# Mosaic-G5.net
KiCad netlist of a schematic drawn in Altium Designer
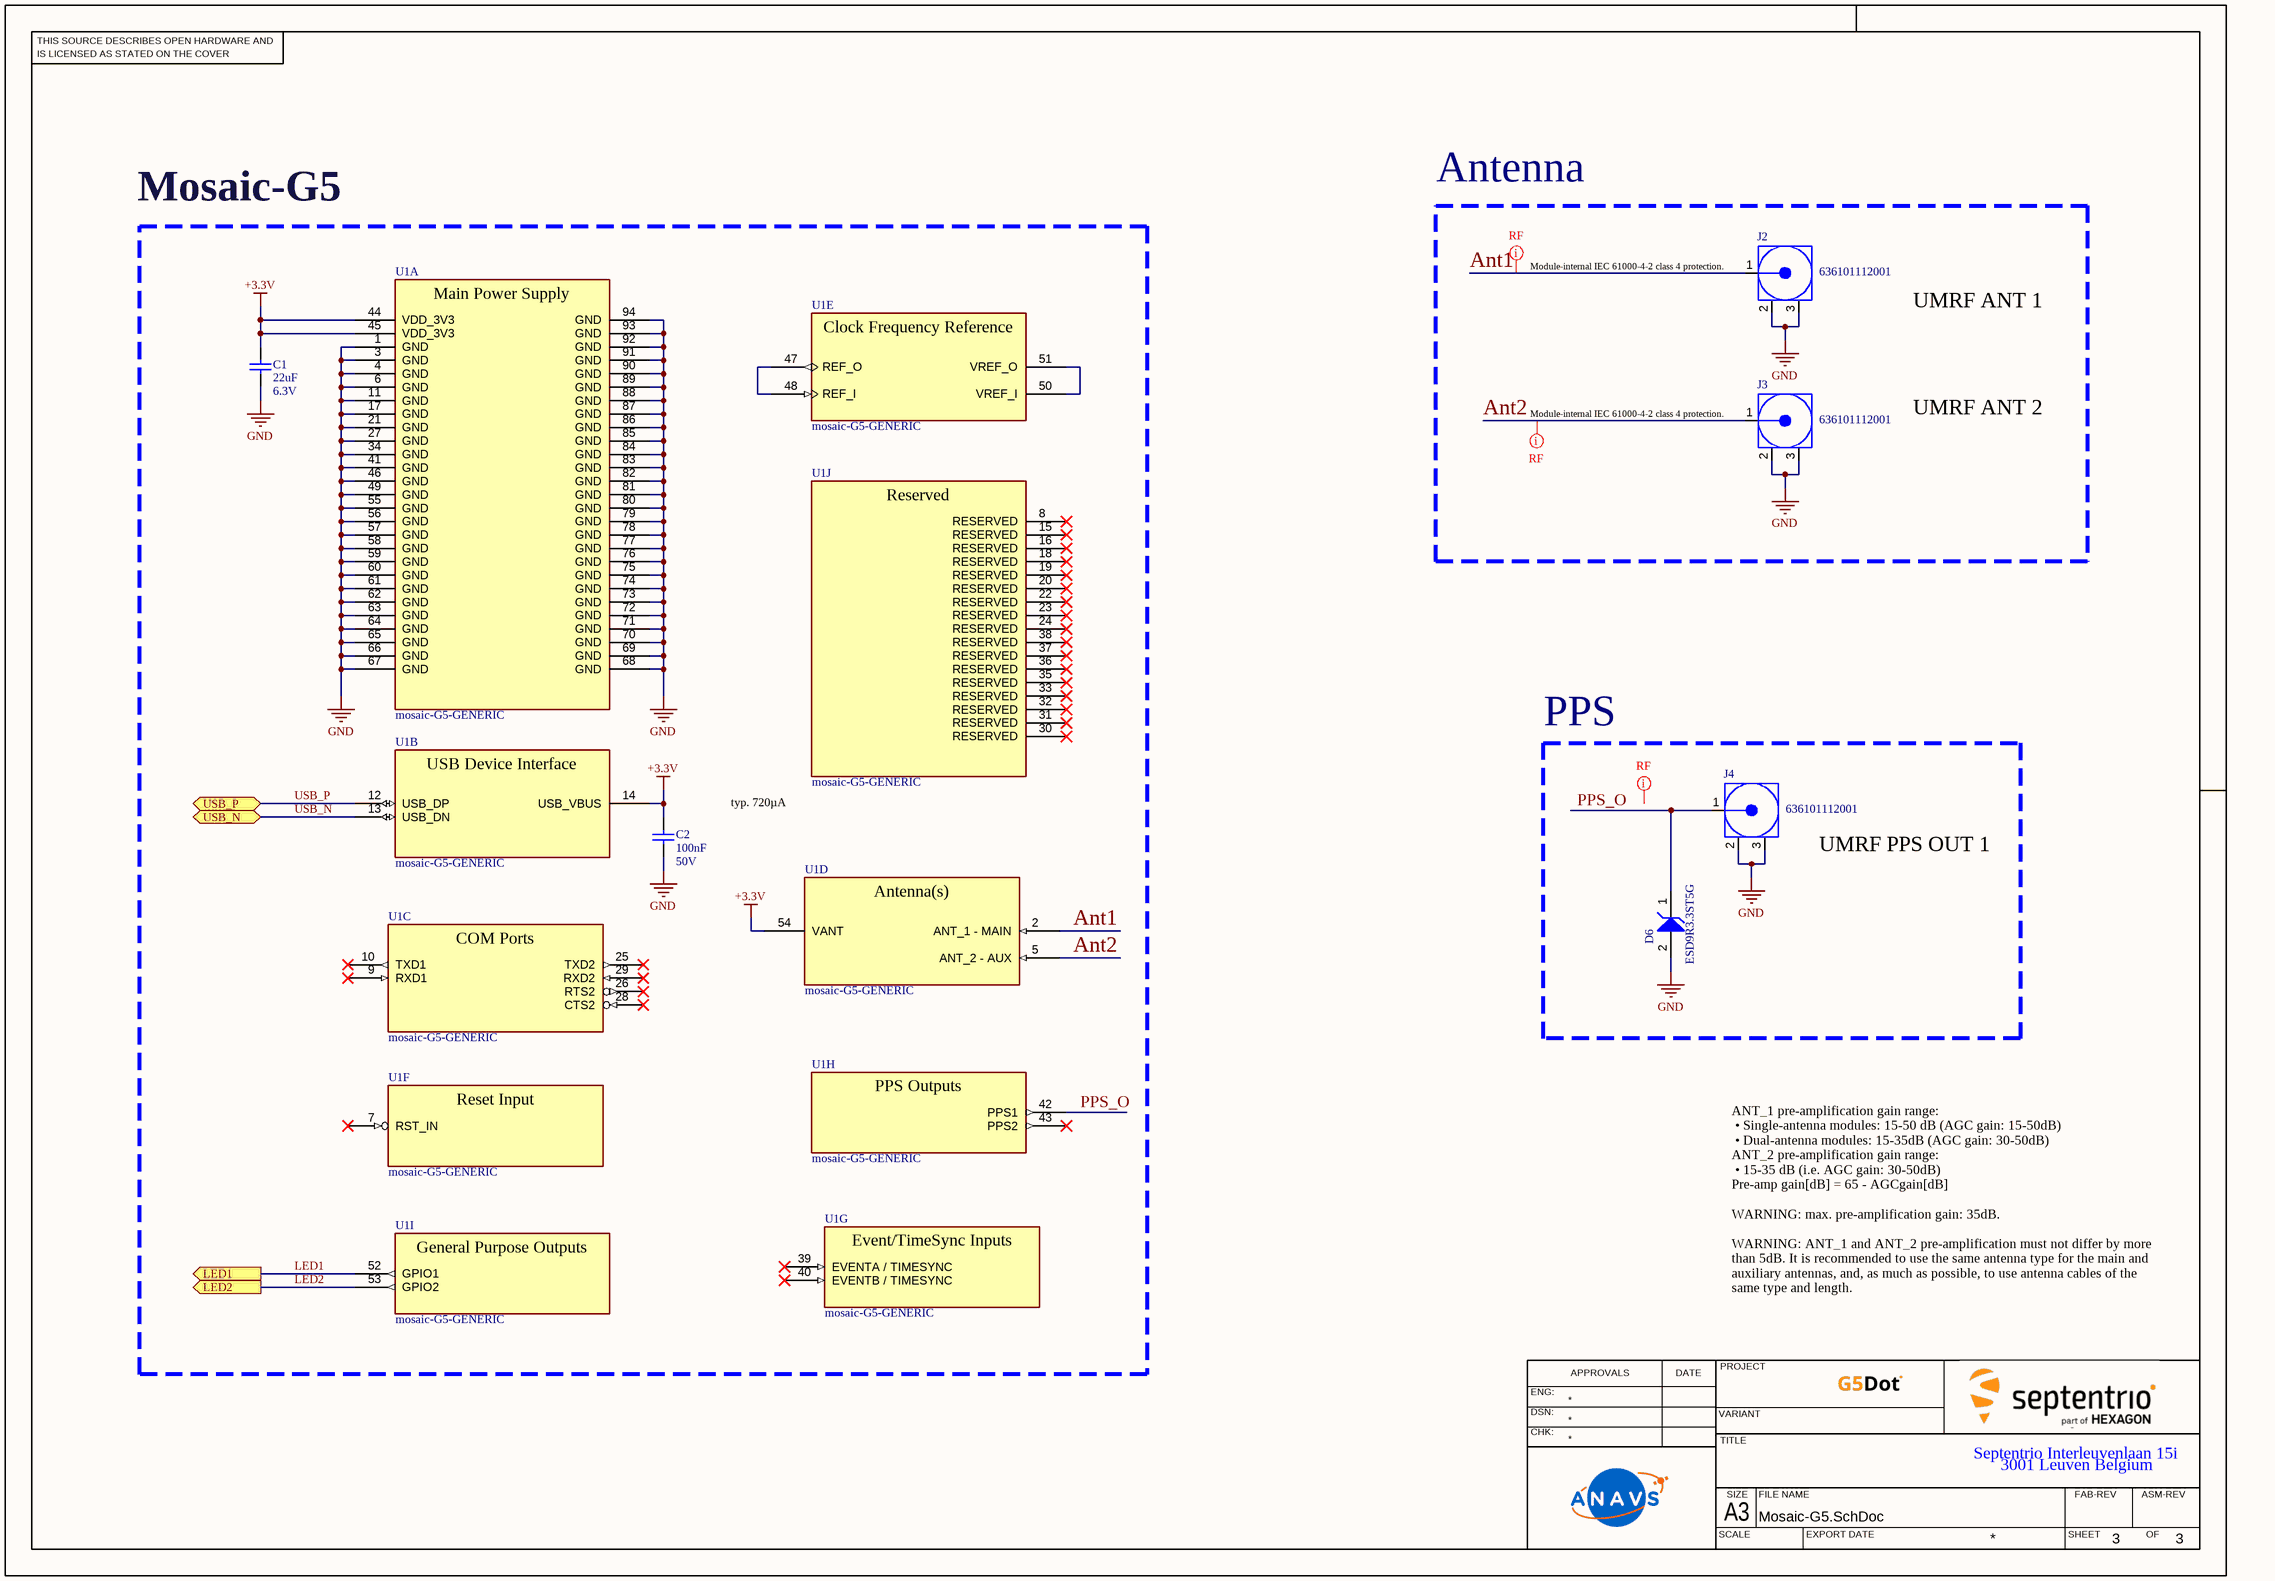
[diagram p0: Mosaic-G5.SchDoc]

(export (version "E")
  (design (tool "Eeschema 10.0.6"))
  (components
    (comp (ref "C1")
      (value "22uF")
      (footprint "CAPC1608X100X20ML10")
      (description "MLCC, 22 uF, 0603, 6.3 V, 20%, X5R")
      (fields
        (field (name "VOLTAGE") "6.3V")
        (field (name "TOLERANCE") "20%")
        (field (name "Comment") "C1608X5R0J226M080AC")
      )
      (libsource (lib "ANavS GmbH") (part "CAP"))
    )
    (comp (ref "C2")
      (value "GCM155R71H104KE02D")
      (footprint "CAP0402C")
      (description "MLCC, 100 nF, 0402, 50 V, 10%, X7R")
      (fields
        (field (name "CAPACITANCE") "100nF")
        (field (name "TOLERANCE") "10%")
        (field (name "VOLTAGE") "50V")
      )
      (libsource (lib "ANavS GmbH") (part "CAP"))
    )
    (comp (ref "D6")
      (value "ESD9R3.3ST5G")
      (footprint "ONSC-SOD-923-2-514AB-01_V")
      (description "ESD9R3.3S Series 4.8 V 0.5 pF Uni-Directional ESD Protection Diode - SOD-923")
      (libsource (lib "ANavS GmbH") (part "ONSC-K1A2-2_A"))
    )
    (comp (ref "J2")
      (value "636101112001")
      (footprint "63610111x001")
      (description "Rf Conn, Umrf, Jack, 50 Ohm, Pcb Rohs Compliant: Yes")
      (libsource (lib "ANavS GmbH") (part "Plug_2GND"))
    )
    (comp (ref "J3")
      (value "636101112001")
      (footprint "63610111x001")
      (description "Rf Conn, Umrf, Jack, 50 Ohm, Pcb Rohs Compliant: Yes")
      (libsource (lib "ANavS GmbH") (part "Plug_2GND"))
    )
    (comp (ref "J4")
      (value "636101112001")
      (footprint "63610111x001")
      (description "Rf Conn, Umrf, Jack, 50 Ohm, Pcb Rohs Compliant: Yes")
      (libsource (lib "ANavS GmbH") (part "Plug_2GND"))
    )
    (comp (ref "U1")
      (value "mosaic-G5-GENERIC")
      (footprint "mosaic-G5-GENERIC-Footprint")
      (description "mosaic-G5 GNSS Module - Low-power multi-band multi-constellation GNSS receiver.")
      (fields (field (name "MANUFACTURER") "septentrio"))
      (libsource (lib "") (part "mosaic-G5-Symbol_1"))
    )
  )
  (nets
    (net (code "1") (name "+3.3V") (class "Default")
      (node (ref "C1") (pin "2") (pinfunction "2_2") (pintype "passive"))
      (node (ref "C2") (pin "2") (pinfunction "2_2") (pintype "passive"))
      (node (ref "U1") (pin "14") (pinfunction "USB_VBUS_14") (pintype "power_in"))
      (node (ref "U1") (pin "44") (pinfunction "VDD_3V3_44") (pintype "power_in"))
      (node (ref "U1") (pin "45") (pinfunction "VDD_3V3_45") (pintype "power_in"))
      (node (ref "U1") (pin "54") (pinfunction "VANT_54") (pintype "power_in"))
    )
    (net (code "2") (name "/Ant1") (class "Default")
      (node (ref "J2") (pin "1") (pinfunction "Signal_1") (pintype "passive"))
      (node (ref "U1") (pin "2") (pinfunction "ANT_1_-_MAIN_2") (pintype "input"))
    )
    (net (code "3") (name "/Ant2") (class "Default")
      (node (ref "J3") (pin "1") (pinfunction "Signal_1") (pintype "passive"))
      (node (ref "U1") (pin "5") (pinfunction "ANT_2_-_AUX_5") (pintype "input"))
    )
    (net (code "4") (name "/LED1") (class "Default")
      (node (ref "U1") (pin "52") (pinfunction "GPIO1_52") (pintype "output"))
    )
    (net (code "5") (name "/LED2") (class "Default")
      (node (ref "U1") (pin "53") (pinfunction "GPIO2_53") (pintype "output"))
    )
    (net (code "6") (name "/PPS_O") (class "Default")
      (node (ref "D6") (pin "1") (pinfunction "K_1") (pintype "passive"))
      (node (ref "J4") (pin "1") (pinfunction "Signal_1") (pintype "passive"))
      (node (ref "U1") (pin "42") (pinfunction "PPS1_42") (pintype "output"))
    )
    (net (code "7") (name "/USB_N") (class "Default")
      (node (ref "U1") (pin "13") (pinfunction "USB_DN_13") (pintype "bidirectional"))
    )
    (net (code "8") (name "/USB_P") (class "Default")
      (node (ref "U1") (pin "12") (pinfunction "USB_DP_12") (pintype "bidirectional"))
    )
    (net (code "9") (name "GND") (class "Default")
      (node (ref "C1") (pin "1") (pinfunction "1_1") (pintype "passive"))
      (node (ref "C2") (pin "1") (pinfunction "1_1") (pintype "passive"))
      (node (ref "D6") (pin "2") (pinfunction "A_2") (pintype "passive"))
      (node (ref "J2") (pin "2") (pinfunction "GND_2") (pintype "passive"))
      (node (ref "J2") (pin "3") (pinfunction "GND_3") (pintype "passive"))
      (node (ref "J3") (pin "2") (pinfunction "GND_2") (pintype "passive"))
      (node (ref "J3") (pin "3") (pinfunction "GND_3") (pintype "passive"))
      (node (ref "J4") (pin "2") (pinfunction "GND_2") (pintype "passive"))
      (node (ref "J4") (pin "3") (pinfunction "GND_3") (pintype "passive"))
      (node (ref "U1") (pin "1") (pinfunction "GND_1") (pintype "power_in"))
      (node (ref "U1") (pin "11") (pinfunction "GND_11") (pintype "power_in"))
      (node (ref "U1") (pin "17") (pinfunction "GND_17") (pintype "power_in"))
      (node (ref "U1") (pin "21") (pinfunction "GND_21") (pintype "power_in"))
      (node (ref "U1") (pin "27") (pinfunction "GND_27") (pintype "power_in"))
      (node (ref "U1") (pin "3") (pinfunction "GND_3") (pintype "power_in"))
      (node (ref "U1") (pin "34") (pinfunction "GND_34") (pintype "power_in"))
      (node (ref "U1") (pin "4") (pinfunction "GND_4") (pintype "power_in"))
      (node (ref "U1") (pin "41") (pinfunction "GND_41") (pintype "power_in"))
      (node (ref "U1") (pin "46") (pinfunction "GND_46") (pintype "power_in"))
      (node (ref "U1") (pin "49") (pinfunction "GND_49") (pintype "power_in"))
      (node (ref "U1") (pin "55") (pinfunction "GND_55") (pintype "power_in"))
      (node (ref "U1") (pin "56") (pinfunction "GND_56") (pintype "power_in"))
      (node (ref "U1") (pin "57") (pinfunction "GND_57") (pintype "power_in"))
      (node (ref "U1") (pin "58") (pinfunction "GND_58") (pintype "power_in"))
      (node (ref "U1") (pin "59") (pinfunction "GND_59") (pintype "power_in"))
      (node (ref "U1") (pin "6") (pinfunction "GND_6") (pintype "power_in"))
      (node (ref "U1") (pin "60") (pinfunction "GND_60") (pintype "power_in"))
      (node (ref "U1") (pin "61") (pinfunction "GND_61") (pintype "power_in"))
      (node (ref "U1") (pin "62") (pinfunction "GND_62") (pintype "power_in"))
      (node (ref "U1") (pin "63") (pinfunction "GND_63") (pintype "power_in"))
      (node (ref "U1") (pin "64") (pinfunction "GND_64") (pintype "power_in"))
      (node (ref "U1") (pin "65") (pinfunction "GND_65") (pintype "power_in"))
      (node (ref "U1") (pin "66") (pinfunction "GND_66") (pintype "power_in"))
      (node (ref "U1") (pin "67") (pinfunction "GND_67") (pintype "power_in"))
      (node (ref "U1") (pin "68") (pinfunction "GND_68") (pintype "power_in"))
      (node (ref "U1") (pin "69") (pinfunction "GND_69") (pintype "power_in"))
      (node (ref "U1") (pin "70") (pinfunction "GND_70") (pintype "power_in"))
      (node (ref "U1") (pin "71") (pinfunction "GND_71") (pintype "power_in"))
      (node (ref "U1") (pin "72") (pinfunction "GND_72") (pintype "power_in"))
      (node (ref "U1") (pin "73") (pinfunction "GND_73") (pintype "power_in"))
      (node (ref "U1") (pin "74") (pinfunction "GND_74") (pintype "power_in"))
      (node (ref "U1") (pin "75") (pinfunction "GND_75") (pintype "power_in"))
      (node (ref "U1") (pin "76") (pinfunction "GND_76") (pintype "power_in"))
      (node (ref "U1") (pin "77") (pinfunction "GND_77") (pintype "power_in"))
      (node (ref "U1") (pin "78") (pinfunction "GND_78") (pintype "power_in"))
      (node (ref "U1") (pin "79") (pinfunction "GND_79") (pintype "power_in"))
      (node (ref "U1") (pin "80") (pinfunction "GND_80") (pintype "power_in"))
      (node (ref "U1") (pin "81") (pinfunction "GND_81") (pintype "power_in"))
      (node (ref "U1") (pin "82") (pinfunction "GND_82") (pintype "power_in"))
      (node (ref "U1") (pin "83") (pinfunction "GND_83") (pintype "power_in"))
      (node (ref "U1") (pin "84") (pinfunction "GND_84") (pintype "power_in"))
      (node (ref "U1") (pin "85") (pinfunction "GND_85") (pintype "power_in"))
      (node (ref "U1") (pin "86") (pinfunction "GND_86") (pintype "power_in"))
      (node (ref "U1") (pin "87") (pinfunction "GND_87") (pintype "power_in"))
      (node (ref "U1") (pin "88") (pinfunction "GND_88") (pintype "power_in"))
      (node (ref "U1") (pin "89") (pinfunction "GND_89") (pintype "power_in"))
      (node (ref "U1") (pin "90") (pinfunction "GND_90") (pintype "power_in"))
      (node (ref "U1") (pin "91") (pinfunction "GND_91") (pintype "power_in"))
      (node (ref "U1") (pin "92") (pinfunction "GND_92") (pintype "power_in"))
      (node (ref "U1") (pin "93") (pinfunction "GND_93") (pintype "power_in"))
      (node (ref "U1") (pin "94") (pinfunction "GND_94") (pintype "power_in"))
    )
    (net (code "10") (name "Net-(U1E-REF_I)") (class "Default")
      (node (ref "U1") (pin "47") (pinfunction "REF_O_47") (pintype "output"))
      (node (ref "U1") (pin "48") (pinfunction "REF_I_48") (pintype "input"))
    )
    (net (code "11") (name "Net-(U1E-VREF_I)") (class "Default")
      (node (ref "U1") (pin "50") (pinfunction "VREF_I_50") (pintype "power_in"))
      (node (ref "U1") (pin "51") (pinfunction "VREF_O_51") (pintype "power_in"))
    )
    (net (code "12") (name "unconnected-(U1C-CTS2-Pad28)") (class "Default")
      (node (ref "U1") (pin "28") (pinfunction "CTS2_28") (pintype "input+no_connect"))
    )
    (net (code "13") (name "unconnected-(U1C-RTS2-Pad26)") (class "Default")
      (node (ref "U1") (pin "26") (pinfunction "RTS2_26") (pintype "output+no_connect"))
    )
    (net (code "14") (name "unconnected-(U1C-RXD1-Pad9)") (class "Default")
      (node (ref "U1") (pin "9") (pinfunction "RXD1_9") (pintype "input+no_connect"))
    )
    (net (code "15") (name "unconnected-(U1C-RXD2-Pad29)") (class "Default")
      (node (ref "U1") (pin "29") (pinfunction "RXD2_29") (pintype "input+no_connect"))
    )
    (net (code "16") (name "unconnected-(U1C-TXD1-Pad10)") (class "Default")
      (node (ref "U1") (pin "10") (pinfunction "TXD1_10") (pintype "output+no_connect"))
    )
    (net (code "17") (name "unconnected-(U1C-TXD2-Pad25)") (class "Default")
      (node (ref "U1") (pin "25") (pinfunction "TXD2_25") (pintype "output+no_connect"))
    )
    (net (code "18") (name "unconnected-(U1F-RST_IN-Pad7)") (class "Default")
      (node (ref "U1") (pin "7") (pinfunction "RST_IN_7") (pintype "input+no_connect"))
    )
    (net (code "19") (name "unconnected-(U1G-EVENTA_{slash}_TIMESYNC-Pad39)") (class "Default")
      (node (ref "U1") (pin "39") (pinfunction "EVENTA_/_TIMESYNC_39") (pintype "input+no_connect"))
    )
    (net (code "20") (name "unconnected-(U1G-EVENTB_{slash}_TIMESYNC-Pad40)") (class "Default")
      (node (ref "U1") (pin "40") (pinfunction "EVENTB_/_TIMESYNC_40") (pintype "input+no_connect"))
    )
    (net (code "21") (name "unconnected-(U1H-PPS2-Pad43)") (class "Default")
      (node (ref "U1") (pin "43") (pinfunction "PPS2_43") (pintype "output+no_connect"))
    )
    (net (code "22") (name "unconnected-(U1J-RESERVED-Pad8)") (class "Default")
      (node (ref "U1") (pin "8") (pinfunction "RESERVED_8") (pintype "passive+no_connect"))
    )
    (net (code "23") (name "unconnected-(U1J-RESERVED-Pad15)") (class "Default")
      (node (ref "U1") (pin "15") (pinfunction "RESERVED_15") (pintype "passive+no_connect"))
    )
    (net (code "24") (name "unconnected-(U1J-RESERVED-Pad16)") (class "Default")
      (node (ref "U1") (pin "16") (pinfunction "RESERVED_16") (pintype "passive+no_connect"))
    )
    (net (code "25") (name "unconnected-(U1J-RESERVED-Pad18)") (class "Default")
      (node (ref "U1") (pin "18") (pinfunction "RESERVED_18") (pintype "passive+no_connect"))
    )
    (net (code "26") (name "unconnected-(U1J-RESERVED-Pad19)") (class "Default")
      (node (ref "U1") (pin "19") (pinfunction "RESERVED_19") (pintype "passive+no_connect"))
    )
    (net (code "27") (name "unconnected-(U1J-RESERVED-Pad20)") (class "Default")
      (node (ref "U1") (pin "20") (pinfunction "RESERVED_20") (pintype "passive+no_connect"))
    )
    (net (code "28") (name "unconnected-(U1J-RESERVED-Pad22)") (class "Default")
      (node (ref "U1") (pin "22") (pinfunction "RESERVED_22") (pintype "passive+no_connect"))
    )
    (net (code "29") (name "unconnected-(U1J-RESERVED-Pad23)") (class "Default")
      (node (ref "U1") (pin "23") (pinfunction "RESERVED_23") (pintype "passive+no_connect"))
    )
    (net (code "30") (name "unconnected-(U1J-RESERVED-Pad24)") (class "Default")
      (node (ref "U1") (pin "24") (pinfunction "RESERVED_24") (pintype "passive+no_connect"))
    )
    (net (code "31") (name "unconnected-(U1J-RESERVED-Pad30)") (class "Default")
      (node (ref "U1") (pin "30") (pinfunction "RESERVED_30") (pintype "passive+no_connect"))
    )
    (net (code "32") (name "unconnected-(U1J-RESERVED-Pad31)") (class "Default")
      (node (ref "U1") (pin "31") (pinfunction "RESERVED_31") (pintype "passive+no_connect"))
    )
    (net (code "33") (name "unconnected-(U1J-RESERVED-Pad32)") (class "Default")
      (node (ref "U1") (pin "32") (pinfunction "RESERVED_32") (pintype "passive+no_connect"))
    )
    (net (code "34") (name "unconnected-(U1J-RESERVED-Pad33)") (class "Default")
      (node (ref "U1") (pin "33") (pinfunction "RESERVED_33") (pintype "passive+no_connect"))
    )
    (net (code "35") (name "unconnected-(U1J-RESERVED-Pad35)") (class "Default")
      (node (ref "U1") (pin "35") (pinfunction "RESERVED_35") (pintype "passive+no_connect"))
    )
    (net (code "36") (name "unconnected-(U1J-RESERVED-Pad36)") (class "Default")
      (node (ref "U1") (pin "36") (pinfunction "RESERVED_36") (pintype "passive+no_connect"))
    )
    (net (code "37") (name "unconnected-(U1J-RESERVED-Pad37)") (class "Default")
      (node (ref "U1") (pin "37") (pinfunction "RESERVED_37") (pintype "passive+no_connect"))
    )
    (net (code "38") (name "unconnected-(U1J-RESERVED-Pad38)") (class "Default")
      (node (ref "U1") (pin "38") (pinfunction "RESERVED_38") (pintype "passive+no_connect"))
    )
  )
)
